# Acoustics_Hydrophone_Process.net
KiCad netlist of a schematic drawn in Altium Designer
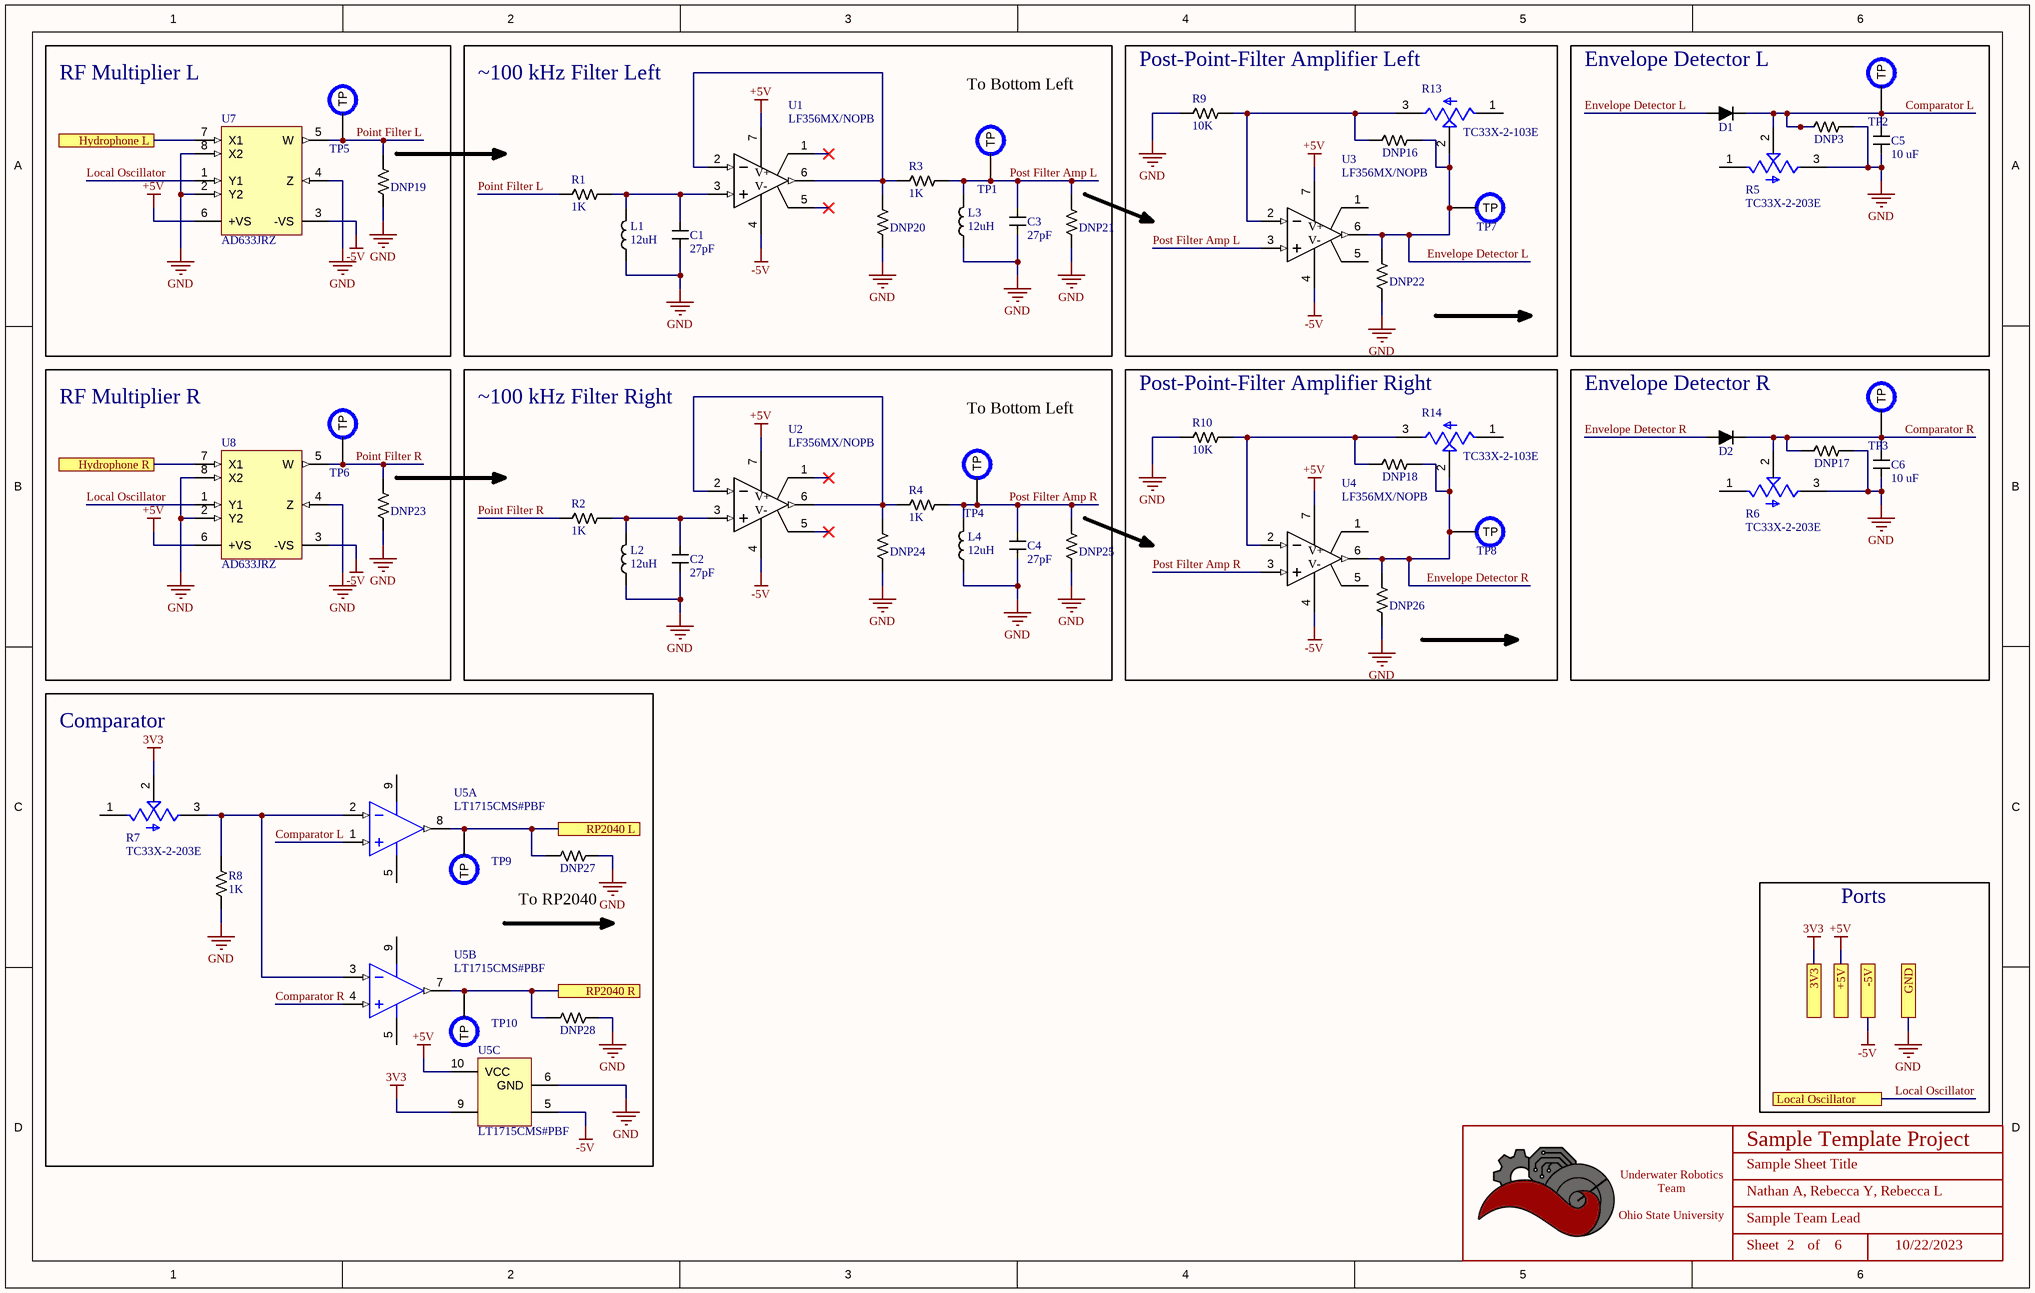
[diagram p0: [Acoustics] Hydrophone Process.SchDoc]

(export (version "E")
  (design (tool "Eeschema 10.0.6"))
  (components
    (comp (ref "C1")
      (value "27pF")
      (footprint "CAPACITOR_0603")
      (description "Cap 27pF 50V +/-5%\r\nCeramic 0603")
      (fields
        (field (name "TOLERANCE") "+/- 5%")
        (field (name "VOLTAGE") "50V")
        (field (name "MADE BY") "Flip B")
      )
      (libsource (lib "Capacitors") (part "CAPACITOR_0.000027uF_0603"))
    )
    (comp (ref "C2")
      (value "27pF")
      (footprint "CAPACITOR_0603")
      (description "Cap 27pF 50V +/-5%\r\nCeramic 0603")
      (fields
        (field (name "TOLERANCE") "+/- 5%")
        (field (name "VOLTAGE") "50V")
        (field (name "MADE BY") "Flip B")
      )
      (libsource (lib "Capacitors") (part "CAPACITOR_0.000027uF_0603"))
    )
    (comp (ref "C3")
      (value "27pF")
      (footprint "CAPACITOR_0603")
      (description "Cap 27pF 50V +/-5%\r\nCeramic 0603")
      (fields
        (field (name "TOLERANCE") "+/- 5%")
        (field (name "VOLTAGE") "50V")
        (field (name "MADE BY") "Flip B")
      )
      (libsource (lib "Capacitors") (part "CAPACITOR_0.000027uF_0603"))
    )
    (comp (ref "C4")
      (value "27pF")
      (footprint "CAPACITOR_0603")
      (description "Cap 27pF 50V +/-5%\r\nCeramic 0603")
      (fields
        (field (name "TOLERANCE") "+/- 5%")
        (field (name "VOLTAGE") "50V")
        (field (name "MADE BY") "Flip B")
      )
      (libsource (lib "Capacitors") (part "CAPACITOR_0.000027uF_0603"))
    )
    (comp (ref "C5")
      (value "10uF Ceramic 6.3V")
      (footprint "CAPACITOR_0603")
      (description "Cap 10uF 6.3V +/-20%\r\nCeramic 0603")
      (fields
        (field (name "TOLERANCE") "+/- 20%")
        (field (name "VOLTAGE") "6.3V")
        (field (name "VALUE (UF)") "10 uF")
        (field (name "MADE BY") "Flip B")
      )
      (libsource (lib "Capacitors") (part "CAPACITOR_10uF_0603"))
    )
    (comp (ref "C6")
      (value "10uF Ceramic 6.3V")
      (footprint "CAPACITOR_0603")
      (description "Cap 10uF 6.3V +/-20%\r\nCeramic 0603")
      (fields
        (field (name "TOLERANCE") "+/- 20%")
        (field (name "VOLTAGE") "6.3V")
        (field (name "VALUE (UF)") "10 uF")
        (field (name "MADE BY") "Flip B")
      )
      (libsource (lib "Capacitors") (part "CAPACITOR_10uF_0603"))
    )
    (comp (ref "D1")
      (value "BAR9002ELE6327XTMA1")
      (footprint "DIODE_0402")
      (description "RF Diode PIN - Single 80V 100 mA 250 mW PG-TSLP-2-19")
      (libsource (lib "Diodes") (part "RF Diode 80V 100mA"))
    )
    (comp (ref "D2")
      (value "BAR9002ELE6327XTMA1")
      (footprint "DIODE_0402")
      (description "RF Diode PIN - Single 80V 100 mA 250 mW PG-TSLP-2-19")
      (libsource (lib "Diodes") (part "RF Diode 80V 100mA"))
    )
    (comp (ref "DNP3")
      (value "DNP")
      (footprint "RESISTOR_0402")
      (description "Do Not Populate 0402")
      (libsource (lib "Resistors") (part "DNP_0402"))
    )
    (comp (ref "DNP16")
      (value "DNP")
      (footprint "RESISTOR_0402")
      (description "Do Not Populate 0402")
      (libsource (lib "Resistors") (part "DNP_0402"))
    )
    (comp (ref "DNP17")
      (value "DNP")
      (footprint "RESISTOR_0402")
      (description "Do Not Populate 0402")
      (libsource (lib "Resistors") (part "DNP_0402"))
    )
    (comp (ref "DNP18")
      (value "DNP")
      (footprint "RESISTOR_0402")
      (description "Do Not Populate 0402")
      (libsource (lib "Resistors") (part "DNP_0402"))
    )
    (comp (ref "DNP19")
      (value "DNP")
      (footprint "RESISTOR_0402")
      (description "Do Not Populate 0402")
      (libsource (lib "Resistors") (part "DNP_0402"))
    )
    (comp (ref "DNP20")
      (value "DNP")
      (footprint "RESISTOR_0402")
      (description "Do Not Populate 0402")
      (libsource (lib "Resistors") (part "DNP_0402"))
    )
    (comp (ref "DNP21")
      (value "DNP")
      (footprint "RESISTOR_0402")
      (description "Do Not Populate 0402")
      (libsource (lib "Resistors") (part "DNP_0402"))
    )
    (comp (ref "DNP22")
      (value "DNP")
      (footprint "RESISTOR_0402")
      (description "Do Not Populate 0402")
      (libsource (lib "Resistors") (part "DNP_0402"))
    )
    (comp (ref "DNP23")
      (value "DNP")
      (footprint "RESISTOR_0402")
      (description "Do Not Populate 0402")
      (libsource (lib "Resistors") (part "DNP_0402"))
    )
    (comp (ref "DNP24")
      (value "DNP")
      (footprint "RESISTOR_0402")
      (description "Do Not Populate 0402")
      (libsource (lib "Resistors") (part "DNP_0402"))
    )
    (comp (ref "DNP25")
      (value "DNP")
      (footprint "RESISTOR_0402")
      (description "Do Not Populate 0402")
      (libsource (lib "Resistors") (part "DNP_0402"))
    )
    (comp (ref "DNP26")
      (value "DNP")
      (footprint "RESISTOR_0402")
      (description "Do Not Populate 0402")
      (libsource (lib "Resistors") (part "DNP_0402"))
    )
    (comp (ref "DNP27")
      (value "DNP")
      (footprint "RESISTOR_0402")
      (description "Do Not Populate 0402")
      (libsource (lib "Resistors") (part "DNP_0402"))
    )
    (comp (ref "DNP28")
      (value "DNP")
      (footprint "RESISTOR_0402")
      (description "Do Not Populate 0402")
      (libsource (lib "Resistors") (part "DNP_0402"))
    )
    (comp (ref "L1")
      (value "12uH")
      (footprint "INDUCTOR_0603")
      (description "12 µH Shielded Multilayer Inductor 10 mA 1.8Ohm Max 0603 (1608 Metric)")
      (fields
        (field (name "TOLERANCE") "+/- 20%")
        (field (name "Comment") "FIXED IND 12UH 10MA 1.8 OHM SMD")
        (field (name "MADE BY") "Robert Pafford")
      )
      (libsource (lib "Inductors") (part "INDUCTOR_12uH_0603"))
    )
    (comp (ref "L2")
      (value "12uH")
      (footprint "INDUCTOR_0603")
      (description "12 µH Shielded Multilayer Inductor 10 mA 1.8Ohm Max 0603 (1608 Metric)")
      (fields
        (field (name "TOLERANCE") "+/- 20%")
        (field (name "Comment") "FIXED IND 12UH 10MA 1.8 OHM SMD")
        (field (name "MADE BY") "Robert Pafford")
      )
      (libsource (lib "Inductors") (part "INDUCTOR_12uH_0603"))
    )
    (comp (ref "L3")
      (value "12uH")
      (footprint "INDUCTOR_0603")
      (description "12 µH Shielded Multilayer Inductor 10 mA 1.8Ohm Max 0603 (1608 Metric)")
      (fields
        (field (name "TOLERANCE") "+/- 20%")
        (field (name "Comment") "FIXED IND 12UH 10MA 1.8 OHM SMD")
        (field (name "MADE BY") "Robert Pafford")
      )
      (libsource (lib "Inductors") (part "INDUCTOR_12uH_0603"))
    )
    (comp (ref "L4")
      (value "12uH")
      (footprint "INDUCTOR_0603")
      (description "12 µH Shielded Multilayer Inductor 10 mA 1.8Ohm Max 0603 (1608 Metric)")
      (fields
        (field (name "TOLERANCE") "+/- 20%")
        (field (name "Comment") "FIXED IND 12UH 10MA 1.8 OHM SMD")
        (field (name "MADE BY") "Robert Pafford")
      )
      (libsource (lib "Inductors") (part "INDUCTOR_12uH_0603"))
    )
    (comp (ref "R1")
      (value "1k Ohm 5% 1/8W")
      (footprint "RESISTOR_0603")
      (description "RES 1k OHM 5% 1/8W 0603")
      (fields
        (field (name "TOLERANCE") "+/- 5%")
        (field (name "VALUE  (OHMS)") "1K")
        (field (name "MADE BY") "Robert Pafford")
      )
      (libsource (lib "Resistors") (part "RESISTOR_1K_0603"))
    )
    (comp (ref "R2")
      (value "1k Ohm 5% 1/8W")
      (footprint "RESISTOR_0603")
      (description "RES 1k OHM 5% 1/8W 0603")
      (fields
        (field (name "TOLERANCE") "+/- 5%")
        (field (name "VALUE  (OHMS)") "1K")
        (field (name "MADE BY") "Robert Pafford")
      )
      (libsource (lib "Resistors") (part "RESISTOR_1K_0603"))
    )
    (comp (ref "R3")
      (value "1k Ohm 5% 1/8W")
      (footprint "RESISTOR_0603")
      (description "RES 1k OHM 5% 1/8W 0603")
      (fields
        (field (name "TOLERANCE") "+/- 5%")
        (field (name "VALUE  (OHMS)") "1K")
        (field (name "MADE BY") "Robert Pafford")
      )
      (libsource (lib "Resistors") (part "RESISTOR_1K_0603"))
    )
    (comp (ref "R4")
      (value "1k Ohm 5% 1/8W")
      (footprint "RESISTOR_0603")
      (description "RES 1k OHM 5% 1/8W 0603")
      (fields
        (field (name "TOLERANCE") "+/- 5%")
        (field (name "VALUE  (OHMS)") "1K")
        (field (name "MADE BY") "Robert Pafford")
      )
      (libsource (lib "Resistors") (part "RESISTOR_1K_0603"))
    )
    (comp (ref "R5")
      (value "TC33X-2-203E")
      (footprint "TRIM_TC33X-2-203E")
      (description "20 kOhms 0.1W, 1/10W J Lead Surface Mount Trimmer Potentiometer Cermet 1 Turn Top Adjustment")
      (fields (field (name "MF") "Bourns") (field (name "DIGI-KEY_PART_NUMBER") "TC33X-2-203ECT-ND"))
      (libsource (lib "Resistors") (part "TC33X-2-203E"))
    )
    (comp (ref "R6")
      (value "TC33X-2-203E")
      (footprint "TRIM_TC33X-2-203E")
      (description "20 kOhms 0.1W, 1/10W J Lead Surface Mount Trimmer Potentiometer Cermet 1 Turn Top Adjustment")
      (fields (field (name "MF") "Bourns") (field (name "DIGI-KEY_PART_NUMBER") "TC33X-2-203ECT-ND"))
      (libsource (lib "Resistors") (part "TC33X-2-203E"))
    )
    (comp (ref "R7")
      (value "TC33X-2-203E")
      (footprint "TRIM_TC33X-2-203E")
      (description "20 kOhms 0.1W, 1/10W J Lead Surface Mount Trimmer Potentiometer Cermet 1 Turn Top Adjustment")
      (fields (field (name "MF") "Bourns") (field (name "DIGI-KEY_PART_NUMBER") "TC33X-2-203ECT-ND"))
      (libsource (lib "Resistors") (part "TC33X-2-203E"))
    )
    (comp (ref "R8")
      (value "1k Ohm 1% 1/16W")
      (footprint "RESISTOR_0402")
      (description "RES 1k OHM 1% 1/16W 0402")
      (fields
        (field (name "TOLERANCE") "+/- 1%")
        (field (name "VALUE  (OHMS)") "1K")
        (field (name "MADE BY") "Robert Pafford")
      )
      (libsource (lib "Resistors") (part "RESISTOR_1K_0402"))
    )
    (comp (ref "R9")
      (value "10k Ohm 0.5% 1/10W")
      (footprint "RESISTOR_0603")
      (description "RES 10k OHM 0.5% 1/10W 0603")
      (fields
        (field (name "TOLERANCE") "+/- 0.5%")
        (field (name "VALUE  (OHMS)") "10K")
        (field (name "MADE BY") "Robert Pafford")
      )
      (libsource (lib "Resistors") (part "RESISTOR_10K_0.5%_0603"))
    )
    (comp (ref "R10")
      (value "10k Ohm 0.5% 1/10W")
      (footprint "RESISTOR_0603")
      (description "RES 10k OHM 0.5% 1/10W 0603")
      (fields
        (field (name "TOLERANCE") "+/- 0.5%")
        (field (name "VALUE  (OHMS)") "10K")
        (field (name "MADE BY") "Robert Pafford")
      )
      (libsource (lib "Resistors") (part "RESISTOR_10K_0.5%_0603"))
    )
    (comp (ref "R13")
      (value "TC33X-2-103E")
      (footprint "TRIM_TC33X-2-203E")
      (description "20 kOhms 0.1W, 1/10W J Lead Surface Mount Trimmer Potentiometer Cermet 1 Turn Top Adjustment")
      (fields (field (name "MF") "Bourns") (field (name "DIGI-KEY_PART_NUMBER") "TC33X-2-203ECT-ND"))
      (libsource (lib "Resistors") (part "TC33X-2-203E"))
    )
    (comp (ref "R14")
      (value "TC33X-2-103E")
      (footprint "TRIM_TC33X-2-203E")
      (description "20 kOhms 0.1W, 1/10W J Lead Surface Mount Trimmer Potentiometer Cermet 1 Turn Top Adjustment")
      (fields (field (name "MF") "Bourns") (field (name "DIGI-KEY_PART_NUMBER") "TC33X-2-203ECT-ND"))
      (libsource (lib "Resistors") (part "TC33X-2-203E"))
    )
    (comp (ref "TP1")
      (value "PCB Test Point")
      (footprint "TESTPOINT_1.2MM")
      (fields (field (name "MADE BY") "Robert Pafford"))
      (libsource (lib "Connectors") (part "TESTPOINT"))
    )
    (comp (ref "TP2")
      (value "PCB Test Point")
      (footprint "TESTPOINT_1.2MM")
      (fields (field (name "MADE BY") "Robert Pafford"))
      (libsource (lib "Connectors") (part "TESTPOINT"))
    )
    (comp (ref "TP3")
      (value "PCB Test Point")
      (footprint "TESTPOINT_1.2MM")
      (fields (field (name "MADE BY") "Robert Pafford"))
      (libsource (lib "Connectors") (part "TESTPOINT"))
    )
    (comp (ref "TP4")
      (value "PCB Test Point")
      (footprint "TESTPOINT_1.2MM")
      (fields (field (name "MADE BY") "Robert Pafford"))
      (libsource (lib "Connectors") (part "TESTPOINT"))
    )
    (comp (ref "TP5")
      (value "PCB Test Point")
      (footprint "TESTPOINT_1.2MM")
      (fields (field (name "MADE BY") "Robert Pafford"))
      (libsource (lib "Connectors") (part "TESTPOINT"))
    )
    (comp (ref "TP6")
      (value "PCB Test Point")
      (footprint "TESTPOINT_1.2MM")
      (fields (field (name "MADE BY") "Robert Pafford"))
      (libsource (lib "Connectors") (part "TESTPOINT"))
    )
    (comp (ref "TP7")
      (value "PCB Test Point")
      (footprint "TESTPOINT_1.2MM")
      (fields (field (name "MADE BY") "Robert Pafford"))
      (libsource (lib "Connectors") (part "TESTPOINT"))
    )
    (comp (ref "TP8")
      (value "PCB Test Point")
      (footprint "TESTPOINT_1.2MM")
      (fields (field (name "MADE BY") "Robert Pafford"))
      (libsource (lib "Connectors") (part "TESTPOINT"))
    )
    (comp (ref "TP9")
      (value "PCB Test Point")
      (footprint "TESTPOINT_1.2MM")
      (fields (field (name "MADE BY") "Robert Pafford"))
      (libsource (lib "Connectors") (part "TESTPOINT"))
    )
    (comp (ref "TP10")
      (value "PCB Test Point")
      (footprint "TESTPOINT_1.2MM")
      (fields (field (name "MADE BY") "Robert Pafford"))
      (libsource (lib "Connectors") (part "TESTPOINT"))
    )
    (comp (ref "U1")
      (value "LF356MX/NOPB")
      (footprint "SOIC-8")
      (description "IC OPAMP JFET 1 CIRCUIT 8SOIC")
      (fields
        (field (name "PARTNUMBER") "LM8261M5X/NOPB")
        (field (name "MANUFACTURER") "Texas Instruments")
        (field (name "CREATED BY") "Dylan T")
      )
      (libsource (lib "Integrated Circuits") (part "LM356MX/NOPB"))
    )
    (comp (ref "U2")
      (value "LF356MX/NOPB")
      (footprint "SOIC-8")
      (description "IC OPAMP JFET 1 CIRCUIT 8SOIC")
      (fields
        (field (name "PARTNUMBER") "LM8261M5X/NOPB")
        (field (name "MANUFACTURER") "Texas Instruments")
        (field (name "CREATED BY") "Dylan T")
      )
      (libsource (lib "Integrated Circuits") (part "LM356MX/NOPB"))
    )
    (comp (ref "U3")
      (value "LF356MX/NOPB")
      (footprint "SOIC-8")
      (description "IC OPAMP JFET 1 CIRCUIT 8SOIC")
      (fields
        (field (name "PARTNUMBER") "LM8261M5X/NOPB")
        (field (name "MANUFACTURER") "Texas Instruments")
        (field (name "CREATED BY") "Dylan T")
      )
      (libsource (lib "Integrated Circuits") (part "LM356MX/NOPB"))
    )
    (comp (ref "U4")
      (value "LF356MX/NOPB")
      (footprint "SOIC-8")
      (description "IC OPAMP JFET 1 CIRCUIT 8SOIC")
      (fields
        (field (name "PARTNUMBER") "LM8261M5X/NOPB")
        (field (name "MANUFACTURER") "Texas Instruments")
        (field (name "CREATED BY") "Dylan T")
      )
      (libsource (lib "Integrated Circuits") (part "LM356MX/NOPB"))
    )
    (comp (ref "U5")
      (value "LT1715CMS#PBF")
      (footprint "LT-MS10_N")
      (fields (field (name "GENERIC PART NUMBER") "LT1715") (field (name "MANUFACTURER") "Linear Technology"))
      (libsource (lib "") (part "LT-LT1715-MSOP10_1"))
    )
    (comp (ref "U7")
      (value "AD633JRZ")
      (footprint "ADI-R-8_M")
      (description "Low Cost Analog Multiplier, 20 V/us, 6 mA, 0 to 70 degC, 8-Pin SOIC (R), RoHS, Tube")
      (fields (field (name "PARTNUMBER") "AD633"))
      (libsource (lib "Altium Content Vault") (part "ADI-AD633-R-8"))
    )
    (comp (ref "U8")
      (value "AD633JRZ")
      (footprint "ADI-R-8_M")
      (description "Low Cost Analog Multiplier, 20 V/us, 6 mA, 0 to 70 degC, 8-Pin SOIC (R), RoHS, Tube")
      (fields (field (name "PARTNUMBER") "AD633"))
      (libsource (lib "Altium Content Vault") (part "ADI-AD633-R-8"))
    )
  )
  (nets
    (net (code "1") (name "+5V") (class "Default")
      (node (ref "U1") (pin "7") (pinfunction "V+_7") (pintype "power_in"))
      (node (ref "U2") (pin "7") (pinfunction "V+_7") (pintype "power_in"))
      (node (ref "U3") (pin "7") (pinfunction "V+_7") (pintype "power_in"))
      (node (ref "U4") (pin "7") (pinfunction "V+_7") (pintype "power_in"))
      (node (ref "U5") (pin "10") (pinfunction "VCC_10") (pintype "power_in"))
      (node (ref "U7") (pin "6") (pinfunction "+VS_6") (pintype "power_in"))
      (node (ref "U8") (pin "6") (pinfunction "+VS_6") (pintype "power_in"))
    )
    (net (code "2") (name "-5V") (class "Default")
      (node (ref "U1") (pin "4") (pinfunction "V-_4") (pintype "power_in"))
      (node (ref "U2") (pin "4") (pinfunction "V-_4") (pintype "power_in"))
      (node (ref "U3") (pin "4") (pinfunction "V-_4") (pintype "power_in"))
      (node (ref "U4") (pin "4") (pinfunction "V-_4") (pintype "power_in"))
      (node (ref "U5") (pin "5") (pinfunction "VEE_5") (pintype "power_in"))
      (node (ref "U7") (pin "3") (pinfunction "-VS_3") (pintype "power_in"))
      (node (ref "U8") (pin "3") (pinfunction "-VS_3") (pintype "power_in"))
    )
    (net (code "4") (name "/Comparator L") (class "Default")
      (node (ref "C5") (pin "1") (pinfunction "1_1") (pintype "passive"))
      (node (ref "D1") (pin "2") (pinfunction "2_2") (pintype "passive"))
      (node (ref "DNP3") (pin "2") (pinfunction "2_2") (pintype "passive"))
      (node (ref "R5") (pin "2") (pinfunction "W_2") (pintype "passive"))
      (node (ref "TP2") (pin "TP") (pinfunction "TP_TP") (pintype "passive"))
      (node (ref "U5") (pin "1") (pinfunction "+IN_A_1") (pintype "input"))
    )
    (net (code "5") (name "/Comparator R") (class "Default")
      (node (ref "C6") (pin "1") (pinfunction "1_1") (pintype "passive"))
      (node (ref "D2") (pin "2") (pinfunction "2_2") (pintype "passive"))
      (node (ref "DNP17") (pin "2") (pinfunction "2_2") (pintype "passive"))
      (node (ref "R6") (pin "2") (pinfunction "W_2") (pintype "passive"))
      (node (ref "TP3") (pin "TP") (pinfunction "TP_TP") (pintype "passive"))
      (node (ref "U5") (pin "4") (pinfunction "+IN_B_4") (pintype "input"))
    )
    (net (code "6") (name "/Envelope Detector L") (class "Default")
      (node (ref "D1") (pin "1") (pinfunction "1_1") (pintype "passive"))
      (node (ref "DNP16") (pin "1") (pinfunction "1_1") (pintype "passive"))
      (node (ref "DNP22") (pin "1") (pinfunction "1_1") (pintype "passive"))
      (node (ref "R13") (pin "2") (pinfunction "W_2") (pintype "passive"))
      (node (ref "TP7") (pin "TP") (pinfunction "TP_TP") (pintype "passive"))
      (node (ref "U3") (pin "6") (pinfunction "OUT_6") (pintype "output"))
    )
    (net (code "7") (name "/Envelope Detector R") (class "Default")
      (node (ref "D2") (pin "1") (pinfunction "1_1") (pintype "passive"))
      (node (ref "DNP18") (pin "1") (pinfunction "1_1") (pintype "passive"))
      (node (ref "DNP26") (pin "1") (pinfunction "1_1") (pintype "passive"))
      (node (ref "R14") (pin "2") (pinfunction "W_2") (pintype "passive"))
      (node (ref "TP8") (pin "TP") (pinfunction "TP_TP") (pintype "passive"))
      (node (ref "U4") (pin "6") (pinfunction "OUT_6") (pintype "output"))
    )
    (net (code "8") (name "/Hydrophone L") (class "Default")
      (node (ref "U7") (pin "7") (pinfunction "X1_7") (pintype "input"))
    )
    (net (code "9") (name "/Hydrophone R") (class "Default")
      (node (ref "U8") (pin "7") (pinfunction "X1_7") (pintype "input"))
    )
    (net (code "10") (name "/Local Oscillator") (class "Default")
      (node (ref "U7") (pin "1") (pinfunction "Y1_1") (pintype "input"))
      (node (ref "U8") (pin "1") (pinfunction "Y1_1") (pintype "input"))
    )
    (net (code "11") (name "/Point Filter L") (class "Default")
      (node (ref "DNP19") (pin "1") (pinfunction "1_1") (pintype "passive"))
      (node (ref "R1") (pin "2") (pinfunction "2_2") (pintype "passive"))
      (node (ref "TP5") (pin "TP") (pinfunction "TP_TP") (pintype "passive"))
      (node (ref "U7") (pin "5") (pinfunction "W_5") (pintype "output"))
    )
    (net (code "12") (name "/Point Filter R") (class "Default")
      (node (ref "DNP23") (pin "1") (pinfunction "1_1") (pintype "passive"))
      (node (ref "R2") (pin "2") (pinfunction "2_2") (pintype "passive"))
      (node (ref "TP6") (pin "TP") (pinfunction "TP_TP") (pintype "passive"))
      (node (ref "U8") (pin "5") (pinfunction "W_5") (pintype "output"))
    )
    (net (code "13") (name "/Post Filter Amp L") (class "Default")
      (node (ref "C3") (pin "1") (pinfunction "1_1") (pintype "passive"))
      (node (ref "DNP21") (pin "1") (pinfunction "1_1") (pintype "passive"))
      (node (ref "L3") (pin "1") (pinfunction "1_1") (pintype "passive"))
      (node (ref "R3") (pin "1") (pinfunction "1_1") (pintype "passive"))
      (node (ref "TP1") (pin "TP") (pinfunction "TP_TP") (pintype "passive"))
      (node (ref "U3") (pin "3") (pinfunction "IN+_3") (pintype "input"))
    )
    (net (code "14") (name "/Post Filter Amp R") (class "Default")
      (node (ref "C4") (pin "1") (pinfunction "1_1") (pintype "passive"))
      (node (ref "DNP25") (pin "1") (pinfunction "1_1") (pintype "passive"))
      (node (ref "L4") (pin "1") (pinfunction "1_1") (pintype "passive"))
      (node (ref "R4") (pin "1") (pinfunction "1_1") (pintype "passive"))
      (node (ref "TP4") (pin "TP") (pinfunction "TP_TP") (pintype "passive"))
      (node (ref "U4") (pin "3") (pinfunction "IN+_3") (pintype "input"))
    )
    (net (code "15") (name "/RP2040 L") (class "Default")
      (node (ref "DNP27") (pin "1") (pinfunction "1_1") (pintype "passive"))
      (node (ref "TP9") (pin "TP") (pinfunction "TP_TP") (pintype "passive"))
      (node (ref "U5") (pin "8") (pinfunction "OUT_A_8") (pintype "output"))
    )
    (net (code "16") (name "/RP2040 R") (class "Default")
      (node (ref "DNP28") (pin "1") (pinfunction "1_1") (pintype "passive"))
      (node (ref "TP10") (pin "TP") (pinfunction "TP_TP") (pintype "passive"))
      (node (ref "U5") (pin "7") (pinfunction "OUT_B_7") (pintype "output"))
    )
    (net (code "17") (name "3V3") (class "Default")
      (node (ref "R7") (pin "2") (pinfunction "W_2") (pintype "passive"))
      (node (ref "U5") (pin "9") (pinfunction "+VS_9") (pintype "power_in"))
    )
    (net (code "18") (name "GND") (class "Default")
      (node (ref "C1") (pin "2") (pinfunction "2_2") (pintype "passive"))
      (node (ref "C2") (pin "2") (pinfunction "2_2") (pintype "passive"))
      (node (ref "C3") (pin "2") (pinfunction "2_2") (pintype "passive"))
      (node (ref "C4") (pin "2") (pinfunction "2_2") (pintype "passive"))
      (node (ref "C5") (pin "2") (pinfunction "2_2") (pintype "passive"))
      (node (ref "C6") (pin "2") (pinfunction "2_2") (pintype "passive"))
      (node (ref "DNP17") (pin "1") (pinfunction "1_1") (pintype "passive"))
      (node (ref "DNP19") (pin "2") (pinfunction "2_2") (pintype "passive"))
      (node (ref "DNP20") (pin "2") (pinfunction "2_2") (pintype "passive"))
      (node (ref "DNP21") (pin "2") (pinfunction "2_2") (pintype "passive"))
      (node (ref "DNP22") (pin "2") (pinfunction "2_2") (pintype "passive"))
      (node (ref "DNP23") (pin "2") (pinfunction "2_2") (pintype "passive"))
      (node (ref "DNP24") (pin "2") (pinfunction "2_2") (pintype "passive"))
      (node (ref "DNP25") (pin "2") (pinfunction "2_2") (pintype "passive"))
      (node (ref "DNP26") (pin "2") (pinfunction "2_2") (pintype "passive"))
      (node (ref "DNP27") (pin "2") (pinfunction "2_2") (pintype "passive"))
      (node (ref "DNP28") (pin "2") (pinfunction "2_2") (pintype "passive"))
      (node (ref "DNP3") (pin "1") (pinfunction "1_1") (pintype "passive"))
      (node (ref "L1") (pin "2") (pinfunction "2_2") (pintype "passive"))
      (node (ref "L2") (pin "2") (pinfunction "2_2") (pintype "passive"))
      (node (ref "L3") (pin "2") (pinfunction "2_2") (pintype "passive"))
      (node (ref "L4") (pin "2") (pinfunction "2_2") (pintype "passive"))
      (node (ref "R10") (pin "2") (pinfunction "2_2") (pintype "passive"))
      (node (ref "R5") (pin "3") (pinfunction "CW_3") (pintype "passive"))
      (node (ref "R6") (pin "3") (pinfunction "CW_3") (pintype "passive"))
      (node (ref "R8") (pin "2") (pinfunction "2_2") (pintype "passive"))
      (node (ref "R9") (pin "2") (pinfunction "2_2") (pintype "passive"))
      (node (ref "U5") (pin "6") (pinfunction "GND_6") (pintype "power_in"))
      (node (ref "U7") (pin "2") (pinfunction "Y2_2") (pintype "input"))
      (node (ref "U7") (pin "4") (pinfunction "Z_4") (pintype "input"))
      (node (ref "U7") (pin "8") (pinfunction "X2_8") (pintype "input"))
      (node (ref "U8") (pin "2") (pinfunction "Y2_2") (pintype "input"))
      (node (ref "U8") (pin "4") (pinfunction "Z_4") (pintype "input"))
      (node (ref "U8") (pin "8") (pinfunction "X2_8") (pintype "input"))
    )
    (net (code "19") (name "Net-(R7-CW)") (class "Default")
      (node (ref "R7") (pin "3") (pinfunction "CW_3") (pintype "passive"))
      (node (ref "R8") (pin "1") (pinfunction "1_1") (pintype "passive"))
      (node (ref "U5") (pin "2") (pinfunction "-IN_A_2") (pintype "input"))
      (node (ref "U5") (pin "3") (pinfunction "-IN_B_3") (pintype "input"))
    )
    (net (code "20") (name "Net-(R13-CW)") (class "Default")
      (node (ref "DNP16") (pin "2") (pinfunction "2_2") (pintype "passive"))
      (node (ref "R13") (pin "3") (pinfunction "CW_3") (pintype "passive"))
      (node (ref "R9") (pin "1") (pinfunction "1_1") (pintype "passive"))
      (node (ref "U3") (pin "2") (pinfunction "IN-_2") (pintype "input"))
    )
    (net (code "21") (name "Net-(R14-CW)") (class "Default")
      (node (ref "DNP18") (pin "2") (pinfunction "2_2") (pintype "passive"))
      (node (ref "R10") (pin "1") (pinfunction "1_1") (pintype "passive"))
      (node (ref "R14") (pin "3") (pinfunction "CW_3") (pintype "passive"))
      (node (ref "U4") (pin "2") (pinfunction "IN-_2") (pintype "input"))
    )
    (net (code "22") (name "Net-(U1-IN+)") (class "Default")
      (node (ref "C1") (pin "1") (pinfunction "1_1") (pintype "passive"))
      (node (ref "L1") (pin "1") (pinfunction "1_1") (pintype "passive"))
      (node (ref "R1") (pin "1") (pinfunction "1_1") (pintype "passive"))
      (node (ref "U1") (pin "3") (pinfunction "IN+_3") (pintype "input"))
    )
    (net (code "23") (name "Net-(U1-IN-)") (class "Default")
      (node (ref "DNP20") (pin "1") (pinfunction "1_1") (pintype "passive"))
      (node (ref "R3") (pin "2") (pinfunction "2_2") (pintype "passive"))
      (node (ref "U1") (pin "2") (pinfunction "IN-_2") (pintype "input"))
      (node (ref "U1") (pin "6") (pinfunction "OUT_6") (pintype "output"))
    )
    (net (code "24") (name "Net-(U2-IN+)") (class "Default")
      (node (ref "C2") (pin "1") (pinfunction "1_1") (pintype "passive"))
      (node (ref "L2") (pin "1") (pinfunction "1_1") (pintype "passive"))
      (node (ref "R2") (pin "1") (pinfunction "1_1") (pintype "passive"))
      (node (ref "U2") (pin "3") (pinfunction "IN+_3") (pintype "input"))
    )
    (net (code "25") (name "Net-(U2-IN-)") (class "Default")
      (node (ref "DNP24") (pin "1") (pinfunction "1_1") (pintype "passive"))
      (node (ref "R4") (pin "2") (pinfunction "2_2") (pintype "passive"))
      (node (ref "U2") (pin "2") (pinfunction "IN-_2") (pintype "input"))
      (node (ref "U2") (pin "6") (pinfunction "OUT_6") (pintype "output"))
    )
    (net (code "26") (name "unconnected-(R5-CCW-Pad1)") (class "Default")
      (node (ref "R5") (pin "1") (pinfunction "CCW_1") (pintype "passive"))
    )
    (net (code "27") (name "unconnected-(R6-CCW-Pad1)") (class "Default")
      (node (ref "R6") (pin "1") (pinfunction "CCW_1") (pintype "passive"))
    )
    (net (code "28") (name "unconnected-(R7-CCW-Pad1)") (class "Default")
      (node (ref "R7") (pin "1") (pinfunction "CCW_1") (pintype "passive"))
    )
    (net (code "29") (name "unconnected-(R13-CCW-Pad1)") (class "Default")
      (node (ref "R13") (pin "1") (pinfunction "CCW_1") (pintype "passive"))
    )
    (net (code "30") (name "unconnected-(R14-CCW-Pad1)") (class "Default")
      (node (ref "R14") (pin "1") (pinfunction "CCW_1") (pintype "passive"))
    )
    (net (code "31") (name "unconnected-(U1-Balance-Pad1)") (class "Default")
      (node (ref "U1") (pin "1") (pinfunction "Balance_1") (pintype "passive+no_connect"))
    )
    (net (code "32") (name "unconnected-(U1-Balance-Pad5)") (class "Default")
      (node (ref "U1") (pin "5") (pinfunction "Balance_5") (pintype "passive+no_connect"))
    )
    (net (code "33") (name "unconnected-(U2-Balance-Pad1)") (class "Default")
      (node (ref "U2") (pin "1") (pinfunction "Balance_1") (pintype "passive+no_connect"))
    )
    (net (code "34") (name "unconnected-(U2-Balance-Pad5)") (class "Default")
      (node (ref "U2") (pin "5") (pinfunction "Balance_5") (pintype "passive+no_connect"))
    )
    (net (code "35") (name "unconnected-(U3-Balance-Pad1)") (class "Default")
      (node (ref "U3") (pin "1") (pinfunction "Balance_1") (pintype "passive"))
    )
    (net (code "36") (name "unconnected-(U3-Balance-Pad5)") (class "Default")
      (node (ref "U3") (pin "5") (pinfunction "Balance_5") (pintype "passive"))
    )
    (net (code "37") (name "unconnected-(U4-Balance-Pad1)") (class "Default")
      (node (ref "U4") (pin "1") (pinfunction "Balance_1") (pintype "passive"))
    )
    (net (code "38") (name "unconnected-(U4-Balance-Pad5)") (class "Default")
      (node (ref "U4") (pin "5") (pinfunction "Balance_5") (pintype "passive"))
    )
    (net (code "39") (name "unconnected-(U5A-+VS-Pad9)") (class "Default")
      (node (ref "U5") (pin "9") (pinfunction "+VS_9") (pintype "power_in"))
    )
    (net (code "40") (name "unconnected-(U5A-VEE-Pad5)") (class "Default")
      (node (ref "U5") (pin "5") (pinfunction "VEE_5") (pintype "power_in"))
    )
    (net (code "41") (name "unconnected-(U5B-+VS-Pad9)") (class "Default")
      (node (ref "U5") (pin "9") (pinfunction "+VS_9") (pintype "power_in"))
    )
    (net (code "42") (name "unconnected-(U5B-VEE-Pad5)") (class "Default")
      (node (ref "U5") (pin "5") (pinfunction "VEE_5") (pintype "power_in"))
    )
  )
)
